# control.net
KiCad netlist of a schematic drawn in EAGLE
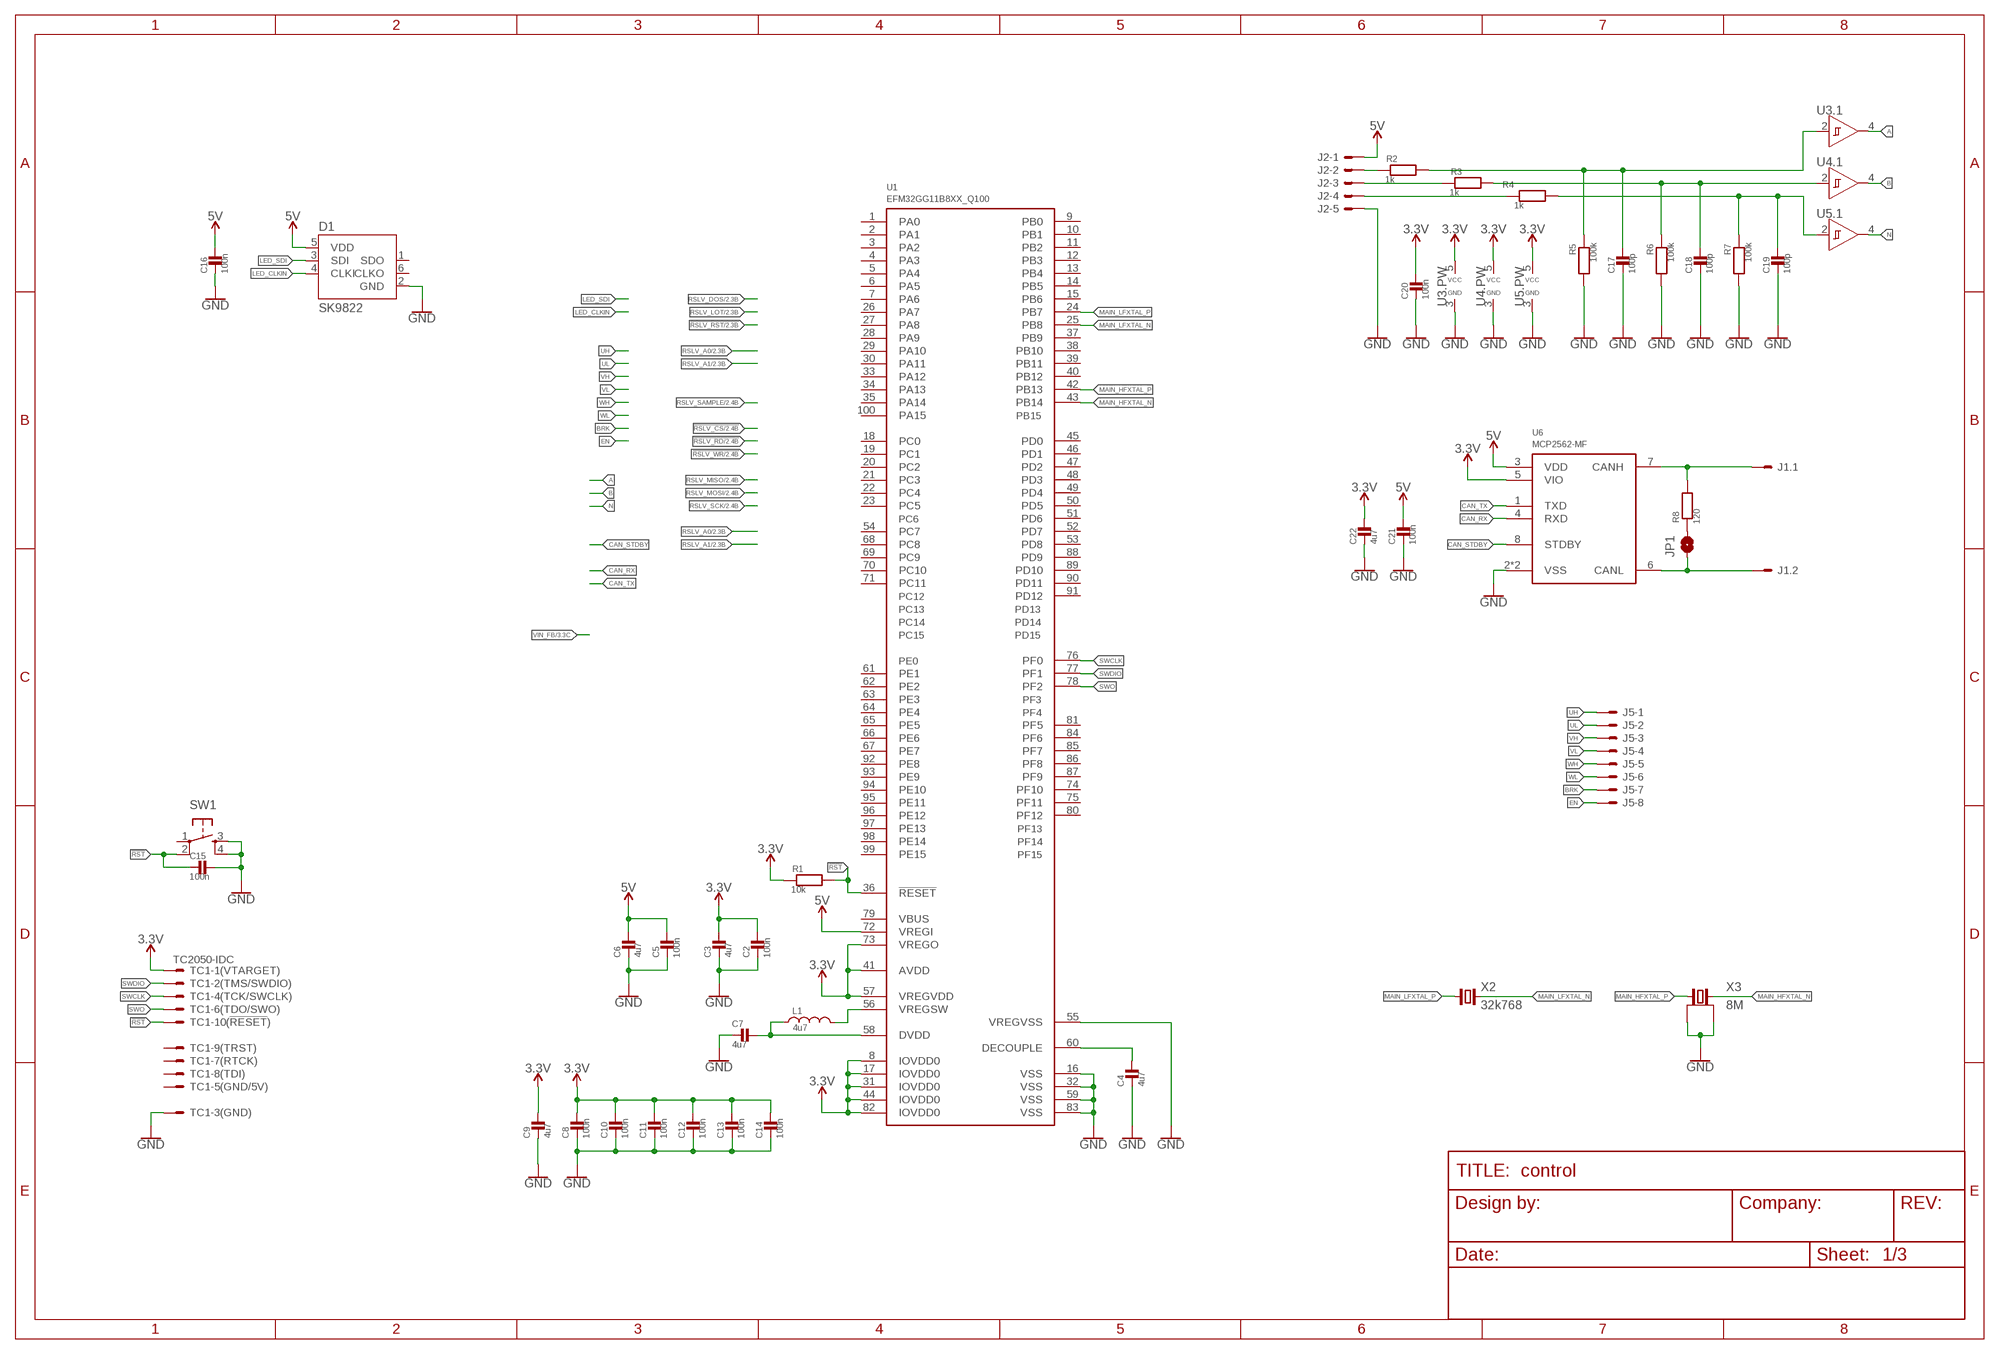
[diagram p0: schematic, sheet 1]
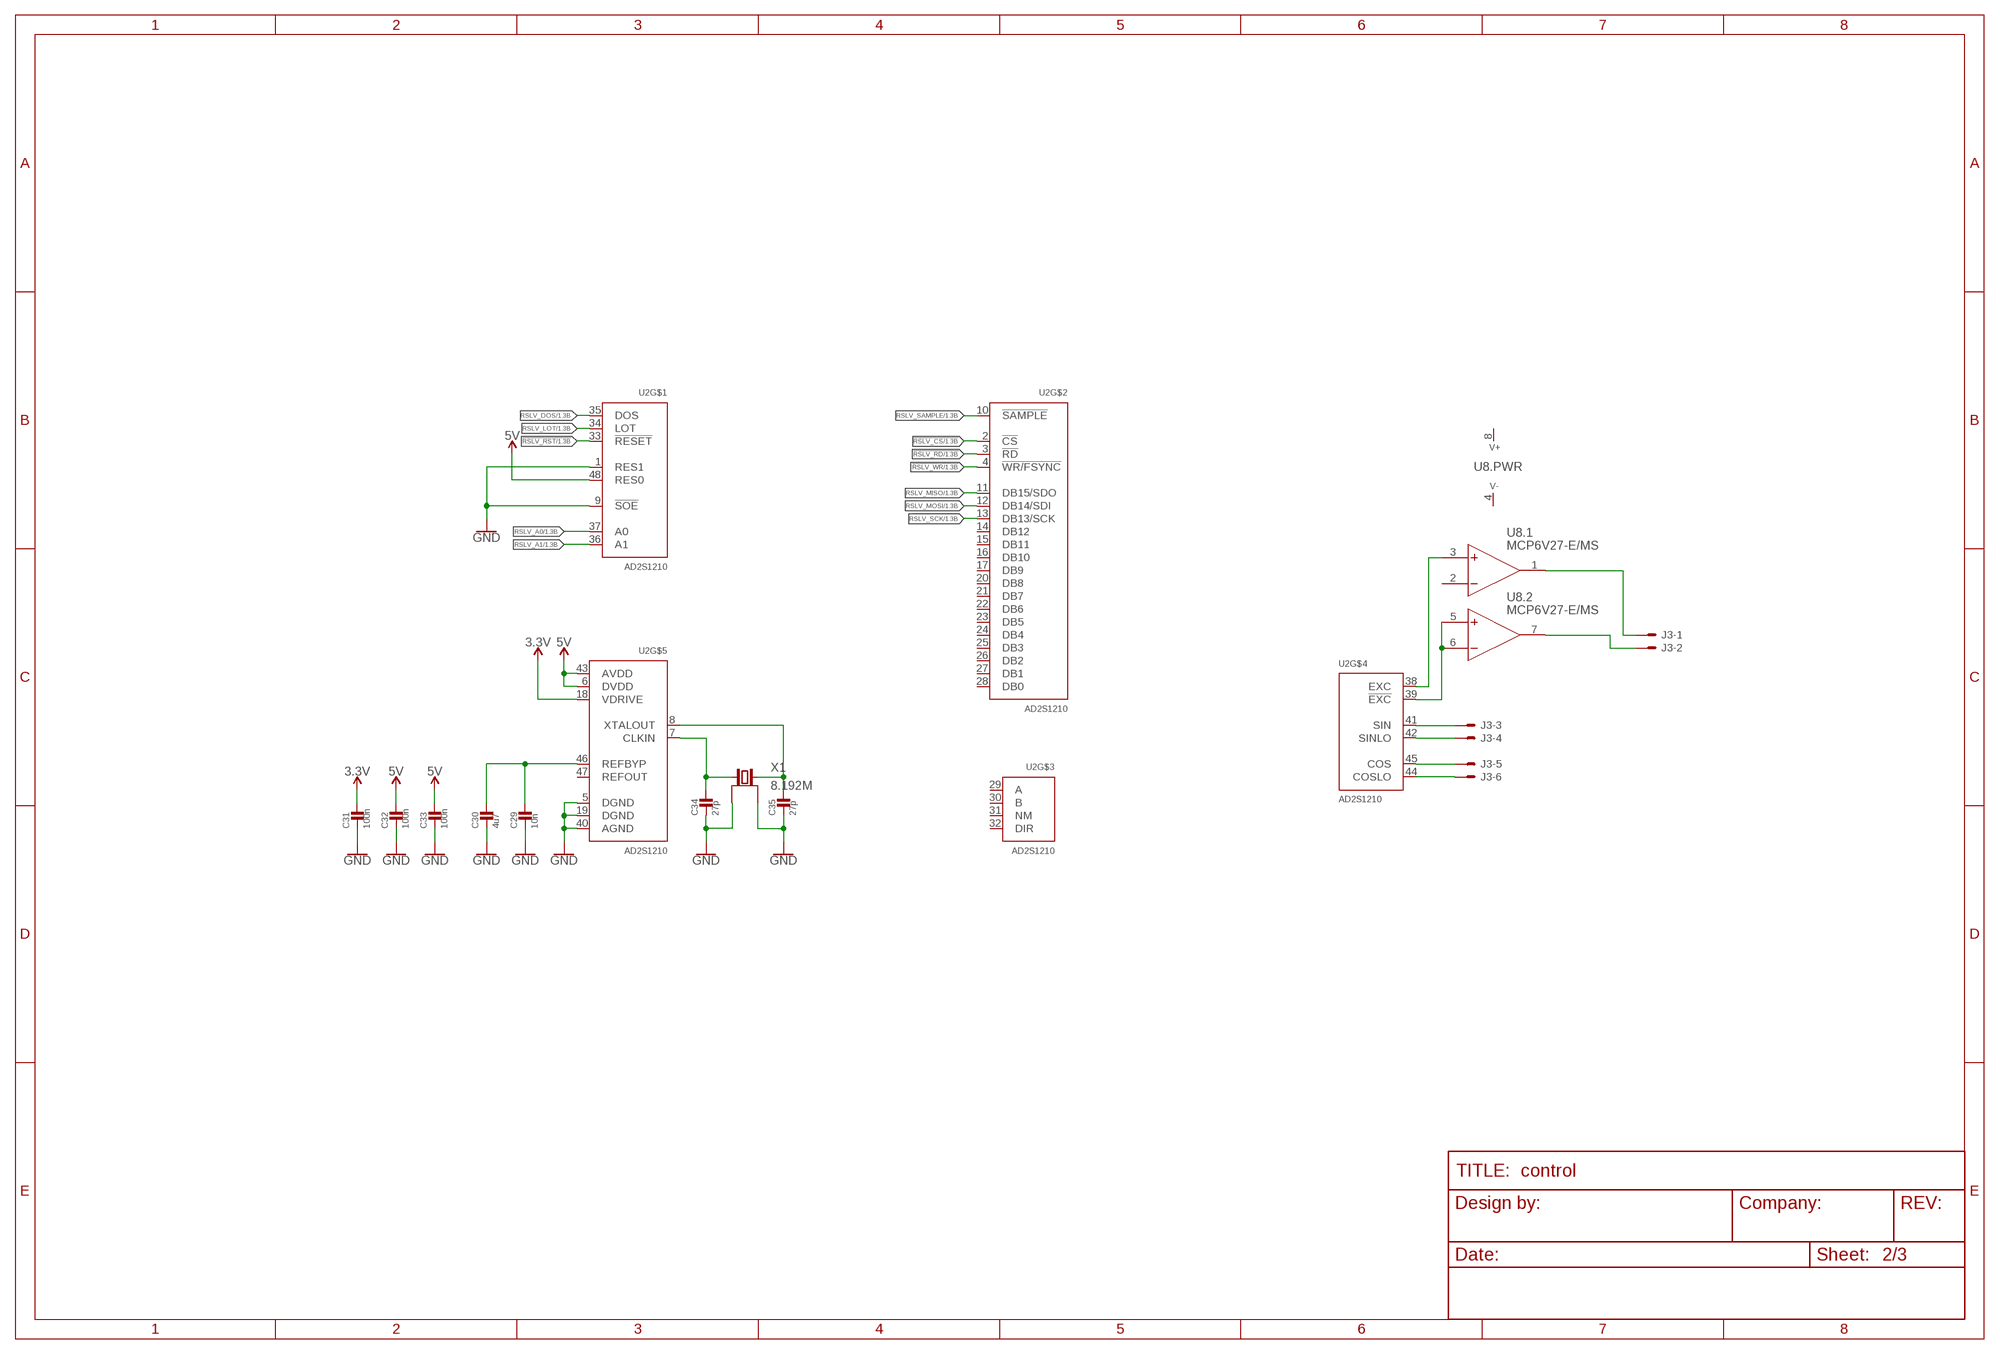
[diagram p1: schematic, sheet 2]
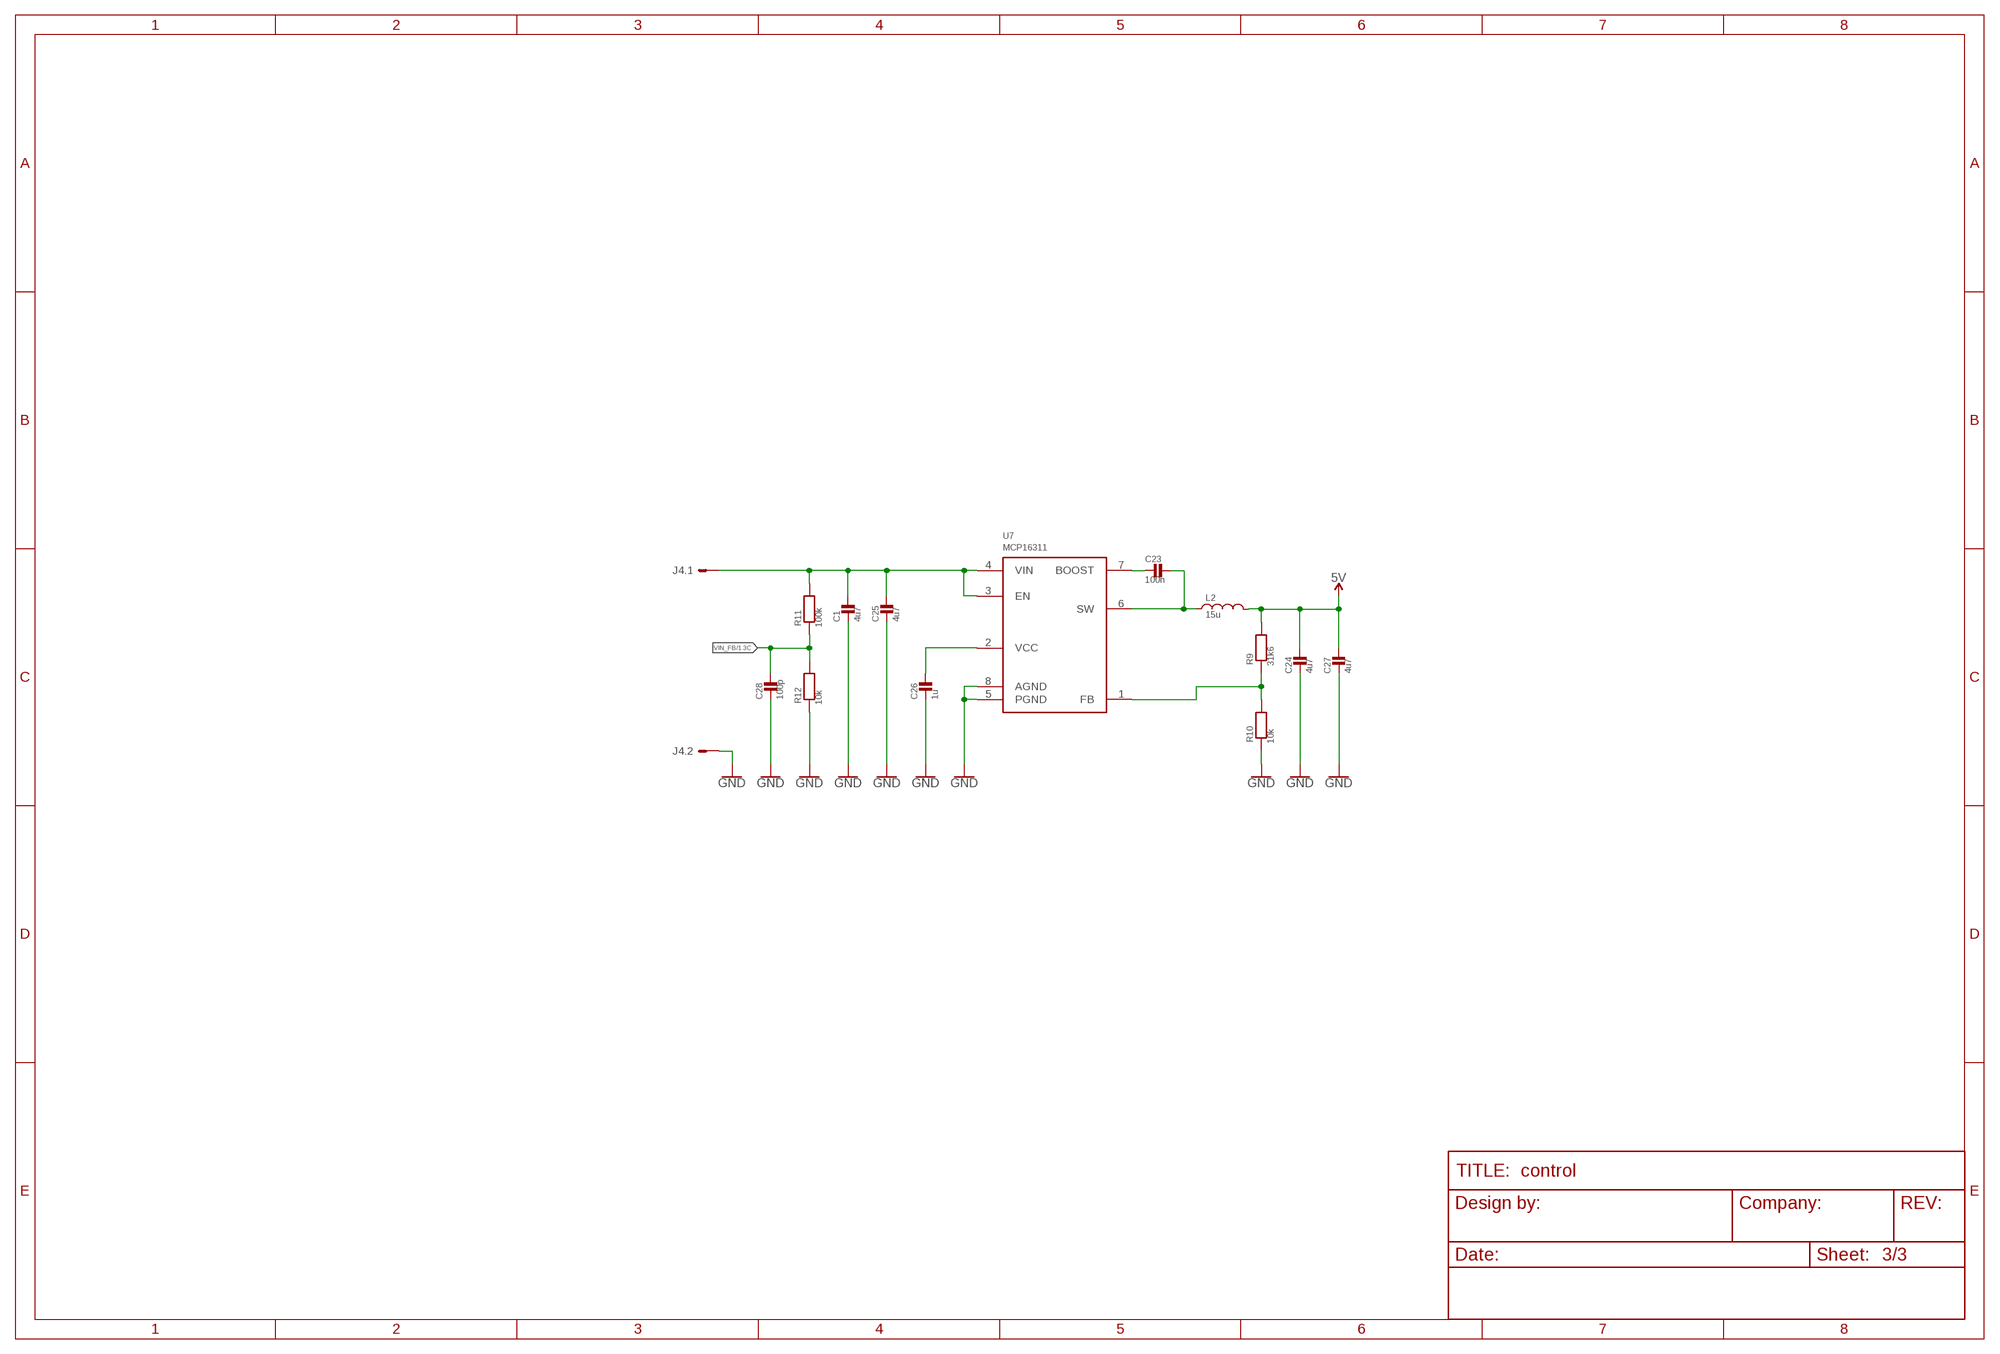
[diagram p2: schematic, sheet 3]

(export (version "E")
  (design (tool "Eeschema 10.0.6"))
  (components
    (comp (ref "C1")
      (value "4u7")
      (footprint "eagle-import:0603_WAVE")
      (libsource (lib "eagle-import") (part "MLCC0603"))
    )
    (comp (ref "C23")
      (value "100n")
      (footprint "eagle-import:0603_WAVE")
      (libsource (lib "eagle-import") (part "MLCC0603"))
    )
    (comp (ref "C24")
      (value "4u7")
      (footprint "eagle-import:0603_WAVE")
      (libsource (lib "eagle-import") (part "MLCC0603"))
    )
    (comp (ref "C25")
      (value "4u7")
      (footprint "eagle-import:0603_WAVE")
      (libsource (lib "eagle-import") (part "MLCC0603"))
    )
    (comp (ref "C26")
      (value "1u")
      (footprint "eagle-import:0603_WAVE")
      (libsource (lib "eagle-import") (part "MLCC0603"))
    )
    (comp (ref "C27")
      (value "4u7")
      (footprint "eagle-import:0603_WAVE")
      (libsource (lib "eagle-import") (part "MLCC0603"))
    )
    (comp (ref "C28")
      (value "100p")
      (footprint "eagle-import:0603_WAVE")
      (libsource (lib "eagle-import") (part "MLCC0603"))
    )
    (comp (ref "J4")
      (value "2EDG-2P")
      (footprint "eagle-import:2EDG-2P")
      (libsource (lib "eagle-import") (part "2EDG-2P"))
    )
    (comp (ref "L2")
      (value "15u")
      (footprint "eagle-import:_0806")
      (libsource (lib "eagle-import") (part "INDUCTOR_NC_0806"))
    )
    (comp (ref "R9")
      (value "31k6")
      (footprint "eagle-import:0603_WAVE")
      (libsource (lib "eagle-import") (part "RESISTOR0603"))
    )
    (comp (ref "R10")
      (value "10k")
      (footprint "eagle-import:0603_WAVE")
      (libsource (lib "eagle-import") (part "RESISTOR0603"))
    )
    (comp (ref "R11")
      (value "100k")
      (footprint "eagle-import:0603_WAVE")
      (libsource (lib "eagle-import") (part "RESISTOR0603"))
    )
    (comp (ref "R12")
      (value "10k")
      (footprint "eagle-import:0603_WAVE")
      (libsource (lib "eagle-import") (part "RESISTOR0603"))
    )
    (comp (ref "U7")
      (value "MCP16311")
      (footprint "eagle-import:MSOP8")
      (libsource (lib "eagle-import") (part "MCP16311"))
    )
    (comp (ref "C29")
      (value "10n")
      (footprint "eagle-import:0603_WAVE")
      (libsource (lib "eagle-import") (part "MLCC0603"))
    )
    (comp (ref "C30")
      (value "4u7")
      (footprint "eagle-import:0603_WAVE")
      (libsource (lib "eagle-import") (part "MLCC0603"))
    )
    (comp (ref "C31")
      (value "100n")
      (footprint "eagle-import:0603_WAVE")
      (libsource (lib "eagle-import") (part "MLCC0603"))
    )
    (comp (ref "C32")
      (value "100n")
      (footprint "eagle-import:0603_WAVE")
      (libsource (lib "eagle-import") (part "MLCC0603"))
    )
    (comp (ref "C33")
      (value "100n")
      (footprint "eagle-import:0603_WAVE")
      (libsource (lib "eagle-import") (part "MLCC0603"))
    )
    (comp (ref "C34")
      (value "27p")
      (footprint "eagle-import:0603_WAVE")
      (libsource (lib "eagle-import") (part "MLCC0603"))
    )
    (comp (ref "C35")
      (value "27p")
      (footprint "eagle-import:0603_WAVE")
      (libsource (lib "eagle-import") (part "MLCC0603"))
    )
    (comp (ref "J3")
      (value "6")
      (footprint "eagle-import:1X6_2.54")
      (libsource (lib "eagle-import") (part "6"))
    )
    (comp (ref "U2")
      (value "AD2S1210")
      (footprint "eagle-import:QFP64")
      (libsource (lib "eagle-import") (part "AD2S1210"))
    )
    (comp (ref "U8")
      (value "MCP6V27-E/MS")
      (footprint "eagle-import:MSOP-8")
      (libsource (lib "eagle-import") (part "MCP6V27-E/MS"))
    )
    (comp (ref "X1")
      (value "8.192M")
      (footprint "eagle-import:4-SMD-3225")
      (libsource (lib "eagle-import") (part "CRYSTAL_4P"))
    )
    (comp (ref "C2")
      (value "100n")
      (footprint "eagle-import:0603_WAVE")
      (libsource (lib "eagle-import") (part "MLCC0603"))
    )
    (comp (ref "C3")
      (value "4u7")
      (footprint "eagle-import:0603_WAVE")
      (libsource (lib "eagle-import") (part "MLCC0603"))
    )
    (comp (ref "C4")
      (value "4u7")
      (footprint "eagle-import:0603_WAVE")
      (libsource (lib "eagle-import") (part "MLCC0603"))
    )
    (comp (ref "C5")
      (value "100n")
      (footprint "eagle-import:0603_WAVE")
      (libsource (lib "eagle-import") (part "MLCC0603"))
    )
    (comp (ref "C6")
      (value "4u7")
      (footprint "eagle-import:0603_WAVE")
      (libsource (lib "eagle-import") (part "MLCC0603"))
    )
    (comp (ref "C7")
      (value "4u7")
      (footprint "eagle-import:0603_WAVE")
      (libsource (lib "eagle-import") (part "MLCC0603"))
    )
    (comp (ref "C8")
      (value "100n")
      (footprint "eagle-import:0603_WAVE")
      (libsource (lib "eagle-import") (part "MLCC0603"))
    )
    (comp (ref "C9")
      (value "4u7")
      (footprint "eagle-import:0603_WAVE")
      (libsource (lib "eagle-import") (part "MLCC0603"))
    )
    (comp (ref "C10")
      (value "100n")
      (footprint "eagle-import:0603_WAVE")
      (libsource (lib "eagle-import") (part "MLCC0603"))
    )
    (comp (ref "C11")
      (value "100n")
      (footprint "eagle-import:0603_WAVE")
      (libsource (lib "eagle-import") (part "MLCC0603"))
    )
    (comp (ref "C12")
      (value "100n")
      (footprint "eagle-import:0603_WAVE")
      (libsource (lib "eagle-import") (part "MLCC0603"))
    )
    (comp (ref "C13")
      (value "100n")
      (footprint "eagle-import:0603_WAVE")
      (libsource (lib "eagle-import") (part "MLCC0603"))
    )
    (comp (ref "C14")
      (value "100n")
      (footprint "eagle-import:0603_WAVE")
      (libsource (lib "eagle-import") (part "MLCC0603"))
    )
    (comp (ref "C15")
      (value "100n")
      (footprint "eagle-import:0603_WAVE")
      (libsource (lib "eagle-import") (part "MLCC0603"))
    )
    (comp (ref "C16")
      (value "100n")
      (footprint "eagle-import:0603_WAVE")
      (libsource (lib "eagle-import") (part "MLCC0603"))
    )
    (comp (ref "C17")
      (value "100p")
      (footprint "eagle-import:0603_WAVE")
      (libsource (lib "eagle-import") (part "MLCC0603"))
    )
    (comp (ref "C18")
      (value "100p")
      (footprint "eagle-import:0603_WAVE")
      (libsource (lib "eagle-import") (part "MLCC0603"))
    )
    (comp (ref "C19")
      (value "100p")
      (footprint "eagle-import:0603_WAVE")
      (libsource (lib "eagle-import") (part "MLCC0603"))
    )
    (comp (ref "C20")
      (value "100n")
      (footprint "eagle-import:0603_WAVE")
      (libsource (lib "eagle-import") (part "MLCC0603"))
    )
    (comp (ref "C21")
      (value "100n")
      (footprint "eagle-import:0603_WAVE")
      (libsource (lib "eagle-import") (part "MLCC0603"))
    )
    (comp (ref "C22")
      (value "4u7")
      (footprint "eagle-import:0603_WAVE")
      (libsource (lib "eagle-import") (part "MLCC0603"))
    )
    (comp (ref "D1")
      (value "SK9822")
      (footprint "eagle-import:2020")
      (libsource (lib "eagle-import") (part "SK9822"))
    )
    (comp (ref "J1")
      (value "2EDG-2P")
      (footprint "eagle-import:2EDG-2P")
      (libsource (lib "eagle-import") (part "2EDG-2P"))
    )
    (comp (ref "J2")
      (value "5")
      (footprint "eagle-import:1X5_2.54")
      (libsource (lib "eagle-import") (part "5"))
    )
    (comp (ref "J5")
      (value "8")
      (footprint "eagle-import:1X8_2.54")
      (libsource (lib "eagle-import") (part "8"))
    )
    (comp (ref "JP1")
      (value "JUMPER-SMT_2_NO_NO-SILK")
      (footprint "eagle-import:SMT-JUMPER_2_NO_NO-SILK")
      (libsource (lib "eagle-import") (part "JUMPER-SMT_2_NO_NO-SILK"))
    )
    (comp (ref "L1")
      (value "4u7")
      (footprint "eagle-import:_0806")
      (libsource (lib "eagle-import") (part "INDUCTOR_NC_0806"))
    )
    (comp (ref "R1")
      (value "10k")
      (footprint "eagle-import:0603_WAVE")
      (libsource (lib "eagle-import") (part "RESISTOR0603"))
    )
    (comp (ref "R2")
      (value "1k")
      (footprint "eagle-import:0603_WAVE")
      (libsource (lib "eagle-import") (part "RESISTOR0603"))
    )
    (comp (ref "R3")
      (value "1k")
      (footprint "eagle-import:0603_WAVE")
      (libsource (lib "eagle-import") (part "RESISTOR0603"))
    )
    (comp (ref "R4")
      (value "1k")
      (footprint "eagle-import:0603_WAVE")
      (libsource (lib "eagle-import") (part "RESISTOR0603"))
    )
    (comp (ref "R5")
      (value "100k")
      (footprint "eagle-import:0603_WAVE")
      (libsource (lib "eagle-import") (part "RESISTOR0603"))
    )
    (comp (ref "R6")
      (value "100k")
      (footprint "eagle-import:0603_WAVE")
      (libsource (lib "eagle-import") (part "RESISTOR0603"))
    )
    (comp (ref "R7")
      (value "100k")
      (footprint "eagle-import:0603_WAVE")
      (libsource (lib "eagle-import") (part "RESISTOR0603"))
    )
    (comp (ref "R8")
      (value "120")
      (footprint "eagle-import:0603_WAVE")
      (libsource (lib "eagle-import") (part "RESISTOR0603"))
    )
    (comp (ref "SW1")
      (value "PUSH_BUTTON")
      (footprint "eagle-import:PUSH_BUTTON")
      (libsource (lib "eagle-import") (part "PUSH_BUTTON"))
    )
    (comp (ref "TC1")
      (value "TC2050-IDC")
      (footprint "eagle-import:TC2050-IDC")
      (libsource (lib "eagle-import") (part "TC2050-IDC"))
    )
    (comp (ref "U1")
      (value "EFM32GG11B8XX_Q100")
      (footprint "eagle-import:QFP100")
      (libsource (lib "eagle-import") (part "EFM32GG11B8XX_Q100"))
    )
    (comp (ref "U3")
      (value "74LVC1G17")
      (footprint "eagle-import:SC70-5")
      (libsource (lib "eagle-import") (part "74LVC1G17"))
    )
    (comp (ref "U4")
      (value "74LVC1G17")
      (footprint "eagle-import:SC70-5")
      (libsource (lib "eagle-import") (part "74LVC1G17"))
    )
    (comp (ref "U5")
      (value "74LVC1G17")
      (footprint "eagle-import:SC70-5")
      (libsource (lib "eagle-import") (part "74LVC1G17"))
    )
    (comp (ref "U6")
      (value "MCP2562-MF")
      (footprint "eagle-import:DFN8")
      (libsource (lib "eagle-import") (part "MCP2562-MF"))
    )
    (comp (ref "X2")
      (value "32k768")
      (footprint "eagle-import:2-SMD-3215")
      (libsource (lib "eagle-import") (part "CRYSTAL2-SMD-3215"))
    )
    (comp (ref "X3")
      (value "8M")
      (footprint "eagle-import:4-SMD-3225")
      (libsource (lib "eagle-import") (part "CRYSTAL_4P"))
    )
  )
  (nets
    (net (code "1") (name "3.3V") (class "Default")
      (node (ref "C10") (pin "P$1") (pinfunction "P$1_P$1") (pintype "bidirectional"))
      (node (ref "C11") (pin "P$1") (pinfunction "P$1_P$1") (pintype "bidirectional"))
      (node (ref "C12") (pin "P$1") (pinfunction "P$1_P$1") (pintype "bidirectional"))
      (node (ref "C13") (pin "P$1") (pinfunction "P$1_P$1") (pintype "bidirectional"))
      (node (ref "C14") (pin "P$1") (pinfunction "P$1_P$1") (pintype "bidirectional"))
      (node (ref "C2") (pin "P$1") (pinfunction "P$1_P$1") (pintype "bidirectional"))
      (node (ref "C20") (pin "P$1") (pinfunction "P$1_P$1") (pintype "bidirectional"))
      (node (ref "C22") (pin "P$1") (pinfunction "P$1_P$1") (pintype "bidirectional"))
      (node (ref "C3") (pin "P$1") (pinfunction "P$1_P$1") (pintype "bidirectional"))
      (node (ref "C31") (pin "P$1") (pinfunction "P$1_P$1") (pintype "bidirectional"))
      (node (ref "C8") (pin "P$1") (pinfunction "P$1_P$1") (pintype "bidirectional"))
      (node (ref "C9") (pin "P$1") (pinfunction "P$1_P$1") (pintype "bidirectional"))
      (node (ref "R1") (pin "P$1") (pinfunction "P$1_P$1") (pintype "bidirectional"))
      (node (ref "TC1") (pin "1") (pinfunction "S_1") (pintype "passive"))
      (node (ref "U1") (pin "17") (pinfunction "IOVDD0_17") (pintype "bidirectional"))
      (node (ref "U1") (pin "31") (pinfunction "IOVDD0_31") (pintype "bidirectional"))
      (node (ref "U1") (pin "41") (pinfunction "AVDD_41") (pintype "bidirectional"))
      (node (ref "U1") (pin "44") (pinfunction "IOVDD0_44") (pintype "bidirectional"))
      (node (ref "U1") (pin "57") (pinfunction "VREGVDD_57") (pintype "bidirectional"))
      (node (ref "U1") (pin "73") (pinfunction "VREGO_73") (pintype "bidirectional"))
      (node (ref "U1") (pin "8") (pinfunction "IOVDD0_8") (pintype "bidirectional"))
      (node (ref "U1") (pin "82") (pinfunction "IOVDD0_82") (pintype "bidirectional"))
      (node (ref "U2") (pin "18") (pinfunction "VDRIVE_18") (pintype "bidirectional"))
      (node (ref "U3") (pin "5") (pinfunction "VCC_5") (pintype "bidirectional"))
      (node (ref "U4") (pin "5") (pinfunction "VCC_5") (pintype "bidirectional"))
      (node (ref "U5") (pin "5") (pinfunction "VCC_5") (pintype "bidirectional"))
      (node (ref "U6") (pin "5") (pinfunction "VIO_5") (pintype "power_in"))
    )
    (net (code "2") (name "5V") (class "Default")
      (node (ref "C16") (pin "P$1") (pinfunction "P$1_P$1") (pintype "bidirectional"))
      (node (ref "C21") (pin "P$1") (pinfunction "P$1_P$1") (pintype "bidirectional"))
      (node (ref "C24") (pin "P$1") (pinfunction "P$1_P$1") (pintype "bidirectional"))
      (node (ref "C27") (pin "P$1") (pinfunction "P$1_P$1") (pintype "bidirectional"))
      (node (ref "C32") (pin "P$1") (pinfunction "P$1_P$1") (pintype "bidirectional"))
      (node (ref "C33") (pin "P$1") (pinfunction "P$1_P$1") (pintype "bidirectional"))
      (node (ref "C5") (pin "P$1") (pinfunction "P$1_P$1") (pintype "bidirectional"))
      (node (ref "C6") (pin "P$1") (pinfunction "P$1_P$1") (pintype "bidirectional"))
      (node (ref "D1") (pin "5") (pinfunction "VDD_5") (pintype "bidirectional"))
      (node (ref "J2") (pin "1") (pinfunction "S_1") (pintype "passive"))
      (node (ref "L2") (pin "2") (pinfunction "P$2_2") (pintype "bidirectional"))
      (node (ref "R9") (pin "P$2") (pinfunction "P$2_P$2") (pintype "bidirectional"))
      (node (ref "U1") (pin "72") (pinfunction "VREGI_72") (pintype "bidirectional"))
      (node (ref "U2") (pin "43") (pinfunction "AVDD_43") (pintype "bidirectional"))
      (node (ref "U2") (pin "48") (pinfunction "RES0_48") (pintype "bidirectional"))
      (node (ref "U2") (pin "6") (pinfunction "DVDD_6") (pintype "bidirectional"))
      (node (ref "U6") (pin "3") (pinfunction "VDD_3") (pintype "power_in"))
    )
    (net (code "3") (name "A") (class "Default")
      (node (ref "U3") (pin "4") (pinfunction "Y_4") (pintype "output"))
    )
    (net (code "4") (name "B") (class "Default")
      (node (ref "U4") (pin "4") (pinfunction "Y_4") (pintype "output"))
    )
    (net (code "5") (name "BRK") (class "Default")
      (node (ref "J5") (pin "7") (pinfunction "S_7") (pintype "passive"))
    )
    (net (code "6") (name "CAN_RX") (class "Default")
      (node (ref "U6") (pin "4") (pinfunction "RXD_4") (pintype "bidirectional"))
    )
    (net (code "7") (name "CAN_STDBY") (class "Default")
      (node (ref "U6") (pin "8") (pinfunction "STDBY_8") (pintype "bidirectional"))
    )
    (net (code "8") (name "CAN_TX") (class "Default")
      (node (ref "U6") (pin "1") (pinfunction "TXD_1") (pintype "bidirectional"))
    )
    (net (code "9") (name "EN") (class "Default")
      (node (ref "J5") (pin "8") (pinfunction "S_8") (pintype "passive"))
    )
    (net (code "10") (name "GND") (class "Default")
      (node (ref "C1") (pin "P$2") (pinfunction "P$2_P$2") (pintype "bidirectional"))
      (node (ref "C10") (pin "P$2") (pinfunction "P$2_P$2") (pintype "bidirectional"))
      (node (ref "C11") (pin "P$2") (pinfunction "P$2_P$2") (pintype "bidirectional"))
      (node (ref "C12") (pin "P$2") (pinfunction "P$2_P$2") (pintype "bidirectional"))
      (node (ref "C13") (pin "P$2") (pinfunction "P$2_P$2") (pintype "bidirectional"))
      (node (ref "C14") (pin "P$2") (pinfunction "P$2_P$2") (pintype "bidirectional"))
      (node (ref "C15") (pin "P$1") (pinfunction "P$1_P$1") (pintype "bidirectional"))
      (node (ref "C16") (pin "P$2") (pinfunction "P$2_P$2") (pintype "bidirectional"))
      (node (ref "C17") (pin "P$2") (pinfunction "P$2_P$2") (pintype "bidirectional"))
      (node (ref "C18") (pin "P$2") (pinfunction "P$2_P$2") (pintype "bidirectional"))
      (node (ref "C19") (pin "P$2") (pinfunction "P$2_P$2") (pintype "bidirectional"))
      (node (ref "C2") (pin "P$2") (pinfunction "P$2_P$2") (pintype "bidirectional"))
      (node (ref "C20") (pin "P$2") (pinfunction "P$2_P$2") (pintype "bidirectional"))
      (node (ref "C21") (pin "P$2") (pinfunction "P$2_P$2") (pintype "bidirectional"))
      (node (ref "C22") (pin "P$2") (pinfunction "P$2_P$2") (pintype "bidirectional"))
      (node (ref "C24") (pin "P$2") (pinfunction "P$2_P$2") (pintype "bidirectional"))
      (node (ref "C25") (pin "P$2") (pinfunction "P$2_P$2") (pintype "bidirectional"))
      (node (ref "C26") (pin "P$2") (pinfunction "P$2_P$2") (pintype "bidirectional"))
      (node (ref "C27") (pin "P$2") (pinfunction "P$2_P$2") (pintype "bidirectional"))
      (node (ref "C28") (pin "P$2") (pinfunction "P$2_P$2") (pintype "bidirectional"))
      (node (ref "C29") (pin "P$2") (pinfunction "P$2_P$2") (pintype "bidirectional"))
      (node (ref "C3") (pin "P$2") (pinfunction "P$2_P$2") (pintype "bidirectional"))
      (node (ref "C30") (pin "P$2") (pinfunction "P$2_P$2") (pintype "bidirectional"))
      (node (ref "C31") (pin "P$2") (pinfunction "P$2_P$2") (pintype "bidirectional"))
      (node (ref "C32") (pin "P$2") (pinfunction "P$2_P$2") (pintype "bidirectional"))
      (node (ref "C33") (pin "P$2") (pinfunction "P$2_P$2") (pintype "bidirectional"))
      (node (ref "C34") (pin "P$2") (pinfunction "P$2_P$2") (pintype "bidirectional"))
      (node (ref "C35") (pin "P$2") (pinfunction "P$2_P$2") (pintype "bidirectional"))
      (node (ref "C4") (pin "P$2") (pinfunction "P$2_P$2") (pintype "bidirectional"))
      (node (ref "C5") (pin "P$2") (pinfunction "P$2_P$2") (pintype "bidirectional"))
      (node (ref "C6") (pin "P$2") (pinfunction "P$2_P$2") (pintype "bidirectional"))
      (node (ref "C7") (pin "P$2") (pinfunction "P$2_P$2") (pintype "bidirectional"))
      (node (ref "C8") (pin "P$2") (pinfunction "P$2_P$2") (pintype "bidirectional"))
      (node (ref "C9") (pin "P$2") (pinfunction "P$2_P$2") (pintype "bidirectional"))
      (node (ref "D1") (pin "2") (pinfunction "GND_2") (pintype "bidirectional"))
      (node (ref "J2") (pin "5") (pinfunction "S_5") (pintype "passive"))
      (node (ref "J4") (pin "P$2") (pinfunction "S_P$2") (pintype "passive"))
      (node (ref "R10") (pin "P$1") (pinfunction "P$1_P$1") (pintype "bidirectional"))
      (node (ref "R12") (pin "P$1") (pinfunction "P$1_P$1") (pintype "bidirectional"))
      (node (ref "R5") (pin "P$2") (pinfunction "P$2_P$2") (pintype "bidirectional"))
      (node (ref "R6") (pin "P$2") (pinfunction "P$2_P$2") (pintype "bidirectional"))
      (node (ref "R7") (pin "P$2") (pinfunction "P$2_P$2") (pintype "bidirectional"))
      (node (ref "SW1") (pin "3") (pinfunction "3_3") (pintype "passive"))
      (node (ref "SW1") (pin "4") (pinfunction "4_4") (pintype "passive"))
      (node (ref "TC1") (pin "3") (pinfunction "S_3") (pintype "passive"))
      (node (ref "U1") (pin "16") (pinfunction "VSS_16") (pintype "bidirectional"))
      (node (ref "U1") (pin "32") (pinfunction "VSS_32") (pintype "bidirectional"))
      (node (ref "U1") (pin "55") (pinfunction "VREGVSS_55") (pintype "bidirectional"))
      (node (ref "U1") (pin "59") (pinfunction "VSS_59") (pintype "bidirectional"))
      (node (ref "U1") (pin "83") (pinfunction "VSS_83") (pintype "bidirectional"))
      (node (ref "U2") (pin "1") (pinfunction "RES1_1") (pintype "bidirectional"))
      (node (ref "U2") (pin "19") (pinfunction "DGND_19") (pintype "bidirectional"))
      (node (ref "U2") (pin "40") (pinfunction "AGND_40") (pintype "bidirectional"))
      (node (ref "U2") (pin "5") (pinfunction "DGND_5") (pintype "bidirectional"))
      (node (ref "U2") (pin "9") (pinfunction "~{SOE}_9") (pintype "bidirectional"))
      (node (ref "U3") (pin "3") (pinfunction "GND_3") (pintype "bidirectional"))
      (node (ref "U4") (pin "3") (pinfunction "GND_3") (pintype "bidirectional"))
      (node (ref "U5") (pin "3") (pinfunction "GND_3") (pintype "bidirectional"))
      (node (ref "U6") (pin "2") (pinfunction "VSS_2") (pintype "power_in"))
      (node (ref "U6") (pin "9") (pinfunction "VSS_9") (pintype "power_in"))
      (node (ref "U7") (pin "5") (pinfunction "PGND_5") (pintype "bidirectional"))
      (node (ref "U7") (pin "8") (pinfunction "AGND_8") (pintype "bidirectional"))
      (node (ref "X1") (pin "2") (pinfunction "GND_2") (pintype "passive"))
      (node (ref "X1") (pin "4") (pinfunction "GND_4") (pintype "passive"))
      (node (ref "X3") (pin "2") (pinfunction "GND_2") (pintype "passive"))
      (node (ref "X3") (pin "4") (pinfunction "GND_4") (pintype "passive"))
    )
    (net (code "11") (name "LED_CLKIN") (class "Default")
      (node (ref "D1") (pin "4") (pinfunction "CLKI_4") (pintype "bidirectional"))
    )
    (net (code "12") (name "LED_SDI") (class "Default")
      (node (ref "D1") (pin "3") (pinfunction "SDI_3") (pintype "bidirectional"))
    )
    (net (code "13") (name "MAIN_HFXTAL_N") (class "Default")
      (node (ref "U1") (pin "43") (pinfunction "PB14_43") (pintype "bidirectional"))
      (node (ref "X3") (pin "3") (pinfunction "2_3") (pintype "passive"))
    )
    (net (code "14") (name "MAIN_HFXTAL_P") (class "Default")
      (node (ref "U1") (pin "42") (pinfunction "PB13_42") (pintype "bidirectional"))
      (node (ref "X3") (pin "1") (pinfunction "1_1") (pintype "passive"))
    )
    (net (code "15") (name "MAIN_LFXTAL_N") (class "Default")
      (node (ref "U1") (pin "25") (pinfunction "PB8_25") (pintype "bidirectional"))
      (node (ref "X2") (pin "2") (pinfunction "2_2") (pintype "passive"))
    )
    (net (code "16") (name "MAIN_LFXTAL_P") (class "Default")
      (node (ref "U1") (pin "24") (pinfunction "PB7_24") (pintype "bidirectional"))
      (node (ref "X2") (pin "1") (pinfunction "1_1") (pintype "passive"))
    )
    (net (code "17") (name "N") (class "Default")
      (node (ref "U5") (pin "4") (pinfunction "Y_4") (pintype "output"))
    )
    (net (code "18") (name "Net-(J1A-S)") (class "Default")
      (node (ref "J1") (pin "P$1") (pinfunction "S_P$1") (pintype "passive"))
      (node (ref "R8") (pin "P$2") (pinfunction "P$2_P$2") (pintype "bidirectional"))
      (node (ref "U6") (pin "7") (pinfunction "CANH_7") (pintype "bidirectional"))
    )
    (net (code "19") (name "Net-(J1B-S)") (class "Default")
      (node (ref "J1") (pin "P$2") (pinfunction "S_P$2") (pintype "passive"))
      (node (ref "JP1") (pin "1") (pinfunction "1_1") (pintype "passive"))
      (node (ref "U6") (pin "6") (pinfunction "CANL_6") (pintype "bidirectional"))
    )
    (net (code "20") (name "Net-(J2B-S)") (class "Default")
      (node (ref "J2") (pin "2") (pinfunction "S_2") (pintype "passive"))
      (node (ref "R2") (pin "P$1") (pinfunction "P$1_P$1") (pintype "bidirectional"))
    )
    (net (code "21") (name "Net-(J2C-S)") (class "Default")
      (node (ref "J2") (pin "3") (pinfunction "S_3") (pintype "passive"))
      (node (ref "R3") (pin "P$1") (pinfunction "P$1_P$1") (pintype "bidirectional"))
    )
    (net (code "22") (name "Net-(J2D-S)") (class "Default")
      (node (ref "J2") (pin "4") (pinfunction "S_4") (pintype "passive"))
      (node (ref "R4") (pin "P$1") (pinfunction "P$1_P$1") (pintype "bidirectional"))
    )
    (net (code "23") (name "Net-(J3A-S)") (class "Default")
      (node (ref "J3") (pin "1") (pinfunction "S_1") (pintype "passive"))
      (node (ref "U8") (pin "1") (pinfunction "OUT_1") (pintype "output"))
    )
    (net (code "24") (name "Net-(J3B-S)") (class "Default")
      (node (ref "J3") (pin "2") (pinfunction "S_2") (pintype "passive"))
      (node (ref "U8") (pin "7") (pinfunction "OUT_7") (pintype "output"))
    )
    (net (code "25") (name "Net-(J3C-S)") (class "Default")
      (node (ref "J3") (pin "3") (pinfunction "S_3") (pintype "passive"))
      (node (ref "U2") (pin "41") (pinfunction "SIN_41") (pintype "bidirectional"))
    )
    (net (code "26") (name "Net-(J3D-S)") (class "Default")
      (node (ref "J3") (pin "4") (pinfunction "S_4") (pintype "passive"))
      (node (ref "U2") (pin "42") (pinfunction "SINLO_42") (pintype "bidirectional"))
    )
    (net (code "27") (name "Net-(J3E-S)") (class "Default")
      (node (ref "J3") (pin "5") (pinfunction "S_5") (pintype "passive"))
      (node (ref "U2") (pin "45") (pinfunction "COS_45") (pintype "bidirectional"))
    )
    (net (code "28") (name "Net-(J3F-S)") (class "Default")
      (node (ref "J3") (pin "6") (pinfunction "S_6") (pintype "passive"))
      (node (ref "U2") (pin "44") (pinfunction "COSLO_44") (pintype "bidirectional"))
    )
    (net (code "29") (name "Net-(J4A-S)") (class "Default")
      (node (ref "C1") (pin "P$1") (pinfunction "P$1_P$1") (pintype "bidirectional"))
      (node (ref "C25") (pin "P$1") (pinfunction "P$1_P$1") (pintype "bidirectional"))
      (node (ref "J4") (pin "P$1") (pinfunction "S_P$1") (pintype "passive"))
      (node (ref "R11") (pin "P$2") (pinfunction "P$2_P$2") (pintype "bidirectional"))
      (node (ref "U7") (pin "3") (pinfunction "EN_3") (pintype "bidirectional"))
      (node (ref "U7") (pin "4") (pinfunction "VIN_4") (pintype "bidirectional"))
    )
    (net (code "30") (name "Net-(JP1-Pad2)") (class "Default")
      (node (ref "JP1") (pin "2") (pinfunction "2_2") (pintype "passive"))
      (node (ref "R8") (pin "P$1") (pinfunction "P$1_P$1") (pintype "bidirectional"))
    )
    (net (code "31") (name "Net-(L1-P$1)") (class "Default")
      (node (ref "C7") (pin "P$1") (pinfunction "P$1_P$1") (pintype "bidirectional"))
      (node (ref "L1") (pin "1") (pinfunction "P$1_1") (pintype "bidirectional"))
      (node (ref "U1") (pin "58") (pinfunction "DVDD_58") (pintype "bidirectional"))
    )
    (net (code "32") (name "Net-(L1-P$2)") (class "Default")
      (node (ref "L1") (pin "2") (pinfunction "P$2_2") (pintype "bidirectional"))
      (node (ref "U1") (pin "56") (pinfunction "VREGSW_56") (pintype "bidirectional"))
    )
    (net (code "33") (name "Net-(L2-P$1)") (class "Default")
      (node (ref "C23") (pin "P$1") (pinfunction "P$1_P$1") (pintype "bidirectional"))
      (node (ref "L2") (pin "1") (pinfunction "P$1_1") (pintype "bidirectional"))
      (node (ref "U7") (pin "6") (pinfunction "SW_6") (pintype "bidirectional"))
    )
    (net (code "34") (name "Net-(U1-DECOUPLE)") (class "Default")
      (node (ref "C4") (pin "P$1") (pinfunction "P$1_P$1") (pintype "bidirectional"))
      (node (ref "U1") (pin "60") (pinfunction "DECOUPLE_60") (pintype "bidirectional"))
    )
    (net (code "35") (name "Net-(U2D-EXC)") (class "Default")
      (node (ref "U2") (pin "38") (pinfunction "EXC_38") (pintype "bidirectional"))
      (node (ref "U8") (pin "3") (pinfunction "+IN_3") (pintype "input"))
    )
    (net (code "36") (name "Net-(U2D-~{EXC})") (class "Default")
      (node (ref "U2") (pin "39") (pinfunction "~{EXC}_39") (pintype "bidirectional"))
      (node (ref "U8") (pin "5") (pinfunction "+IN_5") (pintype "input"))
      (node (ref "U8") (pin "6") (pinfunction "-IN_6") (pintype "input"))
    )
    (net (code "37") (name "Net-(U2E-CLKIN)") (class "Default")
      (node (ref "C34") (pin "P$1") (pinfunction "P$1_P$1") (pintype "bidirectional"))
      (node (ref "U2") (pin "7") (pinfunction "CLKIN_7") (pintype "bidirectional"))
      (node (ref "X1") (pin "1") (pinfunction "1_1") (pintype "passive"))
    )
    (net (code "38") (name "Net-(U2E-REFBYP)") (class "Default")
      (node (ref "C29") (pin "P$1") (pinfunction "P$1_P$1") (pintype "bidirectional"))
      (node (ref "C30") (pin "P$1") (pinfunction "P$1_P$1") (pintype "bidirectional"))
      (node (ref "U2") (pin "46") (pinfunction "REFBYP_46") (pintype "bidirectional"))
    )
    (net (code "39") (name "Net-(U2E-XTALOUT)") (class "Default")
      (node (ref "C35") (pin "P$1") (pinfunction "P$1_P$1") (pintype "bidirectional"))
      (node (ref "U2") (pin "8") (pinfunction "XTALOUT_8") (pintype "bidirectional"))
      (node (ref "X1") (pin "3") (pinfunction "2_3") (pintype "passive"))
    )
    (net (code "40") (name "Net-(U3A-A)") (class "Default")
      (node (ref "C17") (pin "P$1") (pinfunction "P$1_P$1") (pintype "bidirectional"))
      (node (ref "R2") (pin "P$2") (pinfunction "P$2_P$2") (pintype "bidirectional"))
      (node (ref "R5") (pin "P$1") (pinfunction "P$1_P$1") (pintype "bidirectional"))
      (node (ref "U3") (pin "2") (pinfunction "A_2") (pintype "input"))
    )
    (net (code "41") (name "Net-(U4A-A)") (class "Default")
      (node (ref "C18") (pin "P$1") (pinfunction "P$1_P$1") (pintype "bidirectional"))
      (node (ref "R3") (pin "P$2") (pinfunction "P$2_P$2") (pintype "bidirectional"))
      (node (ref "R6") (pin "P$1") (pinfunction "P$1_P$1") (pintype "bidirectional"))
      (node (ref "U4") (pin "2") (pinfunction "A_2") (pintype "input"))
    )
    (net (code "42") (name "Net-(U5A-A)") (class "Default")
      (node (ref "C19") (pin "P$1") (pinfunction "P$1_P$1") (pintype "bidirectional"))
      (node (ref "R4") (pin "P$2") (pinfunction "P$2_P$2") (pintype "bidirectional"))
      (node (ref "R7") (pin "P$1") (pinfunction "P$1_P$1") (pintype "bidirectional"))
      (node (ref "U5") (pin "2") (pinfunction "A_2") (pintype "input"))
    )
    (net (code "43") (name "Net-(U7-BOOST)") (class "Default")
      (node (ref "C23") (pin "P$2") (pinfunction "P$2_P$2") (pintype "bidirectional"))
      (node (ref "U7") (pin "7") (pinfunction "BOOST_7") (pintype "bidirectional"))
    )
    (net (code "44") (name "Net-(U7-FB)") (class "Default")
      (node (ref "R10") (pin "P$2") (pinfunction "P$2_P$2") (pintype "bidirectional"))
      (node (ref "R9") (pin "P$1") (pinfunction "P$1_P$1") (pintype "bidirectional"))
      (node (ref "U7") (pin "1") (pinfunction "FB_1") (pintype "bidirectional"))
    )
    (net (code "45") (name "Net-(U7-VCC)") (class "Default")
      (node (ref "C26") (pin "P$1") (pinfunction "P$1_P$1") (pintype "bidirectional"))
      (node (ref "U7") (pin "2") (pinfunction "VCC_2") (pintype "bidirectional"))
    )
    (net (code "46") (name "RSLV_A0") (class "Default")
      (node (ref "U2") (pin "37") (pinfunction "A0_37") (pintype "bidirectional"))
    )
    (net (code "47") (name "RSLV_A1") (class "Default")
      (node (ref "U2") (pin "36") (pinfunction "A1_36") (pintype "bidirectional"))
    )
    (net (code "48") (name "RSLV_DOS") (class "Default")
      (node (ref "U2") (pin "35") (pinfunction "DOS_35") (pintype "bidirectional"))
    )
    (net (code "49") (name "RSLV_LOT") (class "Default")
      (node (ref "U2") (pin "34") (pinfunction "LOT_34") (pintype "bidirectional"))
    )
    (net (code "50") (name "RSLV_MISO") (class "Default")
      (node (ref "U2") (pin "11") (pinfunction "DB15/SDO_11") (pintype "bidirectional"))
    )
    (net (code "51") (name "RSLV_MOSI") (class "Default")
      (node (ref "U2") (pin "12") (pinfunction "DB14/SDI_12") (pintype "bidirectional"))
    )
    (net (code "52") (name "RSLV_SAMPLE") (class "Default")
      (node (ref "U2") (pin "10") (pinfunction "~{SAMPLE}_10") (pintype "bidirectional"))
    )
    (net (code "53") (name "RSLV_SCK") (class "Default")
      (node (ref "U2") (pin "13") (pinfunction "DB13/SCK_13") (pintype "bidirectional"))
    )
    (net (code "54") (name "SWCLK") (class "Default")
      (node (ref "TC1") (pin "4") (pinfunction "S_4") (pintype "passive"))
      (node (ref "U1") (pin "76") (pinfunction "PF0_76") (pintype "bidirectional"))
    )
    (net (code "55") (name "SWDIO") (class "Default")
      (node (ref "TC1") (pin "2") (pinfunction "S_2") (pintype "passive"))
      (node (ref "U1") (pin "77") (pinfunction "PF1_77") (pintype "bidirectional"))
    )
    (net (code "56") (name "SWO") (class "Default")
      (node (ref "TC1") (pin "6") (pinfunction "S_6") (pintype "passive"))
      (node (ref "U1") (pin "78") (pinfunction "PF2_78") (pintype "bidirectional"))
    )
    (net (code "57") (name "UH") (class "Default")
      (node (ref "J5") (pin "1") (pinfunction "S_1") (pintype "passive"))
    )
    (net (code "58") (name "UL") (class "Default")
      (node (ref "J5") (pin "2") (pinfunction "S_2") (pintype "passive"))
    )
    (net (code "59") (name "V+") (class "Default")
      (node (ref "U8") (pin "8") (pinfunction "V+_8") (pintype "power_in"))
    )
    (net (code "60") (name "V-") (class "Default")
      (node (ref "U8") (pin "4") (pinfunction "V-_4") (pintype "power_in"))
    )
    (net (code "61") (name "VH") (class "Default")
      (node (ref "J5") (pin "3") (pinfunction "S_3") (pintype "passive"))
    )
    (net (code "62") (name "VIN_FB") (class "Default")
      (node (ref "C28") (pin "P$1") (pinfunction "P$1_P$1") (pintype "bidirectional"))
      (node (ref "R11") (pin "P$1") (pinfunction "P$1_P$1") (pintype "bidirectional"))
      (node (ref "R12") (pin "P$2") (pinfunction "P$2_P$2") (pintype "bidirectional"))
    )
    (net (code "63") (name "VL") (class "Default")
      (node (ref "J5") (pin "4") (pinfunction "S_4") (pintype "passive"))
    )
    (net (code "64") (name "WH") (class "Default")
      (node (ref "J5") (pin "5") (pinfunction "S_5") (pintype "passive"))
    )
    (net (code "65") (name "WL") (class "Default")
      (node (ref "J5") (pin "6") (pinfunction "S_6") (pintype "passive"))
    )
    (net (code "66") (name "unconnected-(D1-CLKO-Pad6)") (class "Default")
      (node (ref "D1") (pin "6") (pinfunction "CLKO_6") (pintype "bidirectional"))
    )
    (net (code "67") (name "unconnected-(D1-SDO-Pad1)") (class "Default")
      (node (ref "D1") (pin "1") (pinfunction "SDO_1") (pintype "bidirectional"))
    )
    (net (code "68") (name "unconnected-(SW1-Pad1)") (class "Default")
      (node (ref "SW1") (pin "1") (pinfunction "1_1") (pintype "passive"))
    )
    (net (code "69") (name "unconnected-(TC1F-S-Pad5)") (class "Default")
      (node (ref "TC1") (pin "5") (pinfunction "S_5") (pintype "passive"))
    )
    (net (code "70") (name "unconnected-(TC1H-S-Pad7)") (class "Default")
      (node (ref "TC1") (pin "7") (pinfunction "S_7") (pintype "passive"))
    )
    (net (code "71") (name "unconnected-(TC1I-S-Pad8)") (class "Default")
      (node (ref "TC1") (pin "8") (pinfunction "S_8") (pintype "passive"))
    )
    (net (code "72") (name "unconnected-(TC1J-S-Pad9)") (class "Default")
      (node (ref "TC1") (pin "9") (pinfunction "S_9") (pintype "passive"))
    )
    (net (code "73") (name "unconnected-(U1-PA0-Pad1)") (class "Default")
      (node (ref "U1") (pin "1") (pinfunction "PA0_1") (pintype "bidirectional"))
    )
    (net (code "74") (name "unconnected-(U1-PA1-Pad2)") (class "Default")
      (node (ref "U1") (pin "2") (pinfunction "PA1_2") (pintype "bidirectional"))
    )
    (net (code "75") (name "unconnected-(U1-PA2-Pad3)") (class "Default")
      (node (ref "U1") (pin "3") (pinfunction "PA2_3") (pintype "bidirectional"))
    )
    (net (code "76") (name "unconnected-(U1-PA3-Pad4)") (class "Default")
      (node (ref "U1") (pin "4") (pinfunction "PA3_4") (pintype "bidirectional"))
    )
    (net (code "77") (name "unconnected-(U1-PA4-Pad5)") (class "Default")
      (node (ref "U1") (pin "5") (pinfunction "PA4_5") (pintype "bidirectional"))
    )
    (net (code "78") (name "unconnected-(U1-PA5-Pad6)") (class "Default")
      (node (ref "U1") (pin "6") (pinfunction "PA5_6") (pintype "bidirectional"))
    )
    (net (code "79") (name "unconnected-(U1-PA6-Pad7)") (class "Default")
      (node (ref "U1") (pin "7") (pinfunction "PA6_7") (pintype "bidirectional"))
    )
    (net (code "80") (name "unconnected-(U1-PA7-Pad26)") (class "Default")
      (node (ref "U1") (pin "26") (pinfunction "PA7_26") (pintype "bidirectional"))
    )
    (net (code "81") (name "unconnected-(U1-PA8-Pad27)") (class "Default")
      (node (ref "U1") (pin "27") (pinfunction "PA8_27") (pintype "bidirectional"))
    )
    (net (code "82") (name "unconnected-(U1-PA9-Pad28)") (class "Default")
      (node (ref "U1") (pin "28") (pinfunction "PA9_28") (pintype "bidirectional"))
    )
    (net (code "83") (name "unconnected-(U1-PA10-Pad29)") (class "Default")
      (node (ref "U1") (pin "29") (pinfunction "PA10_29") (pintype "bidirectional"))
    )
    (net (code "84") (name "unconnected-(U1-PA11-Pad30)") (class "Default")
      (node (ref "U1") (pin "30") (pinfunction "PA11_30") (pintype "bidirectional"))
    )
    (net (code "85") (name "unconnected-(U1-PA12-Pad33)") (class "Default")
      (node (ref "U1") (pin "33") (pinfunction "PA12_33") (pintype "bidirectional"))
    )
    (net (code "86") (name "unconnected-(U1-PA13-Pad34)") (class "Default")
      (node (ref "U1") (pin "34") (pinfunction "PA13_34") (pintype "bidirectional"))
    )
    (net (code "87") (name "unconnected-(U1-PA14-Pad35)") (class "Default")
      (node (ref "U1") (pin "35") (pinfunction "PA14_35") (pintype "bidirectional"))
    )
    (net (code "88") (name "unconnected-(U1-PA15-Pad100)") (class "Default")
      (node (ref "U1") (pin "100") (pinfunction "PA15_100") (pintype "bidirectional"))
    )
    (net (code "89") (name "unconnected-(U1-PB0-Pad9)") (class "Default")
      (node (ref "U1") (pin "9") (pinfunction "PB0_9") (pintype "bidirectional"))
    )
    (net (code "90") (name "unconnected-(U1-PB1-Pad10)") (class "Default")
      (node (ref "U1") (pin "10") (pinfunction "PB1_10") (pintype "bidirectional"))
    )
    (net (code "91") (name "unconnected-(U1-PB2-Pad11)") (class "Default")
      (node (ref "U1") (pin "11") (pinfunction "PB2_11") (pintype "bidirectional"))
    )
    (net (code "92") (name "unconnected-(U1-PB3-Pad12)") (class "Default")
      (node (ref "U1") (pin "12") (pinfunction "PB3_12") (pintype "bidirectional"))
    )
    (net (code "93") (name "unconnected-(U1-PB4-Pad13)") (class "Default")
      (node (ref "U1") (pin "13") (pinfunction "PB4_13") (pintype "bidirectional"))
    )
    (net (code "94") (name "unconnected-(U1-PB5-Pad14)") (class "Default")
      (node (ref "U1") (pin "14") (pinfunction "PB5_14") (pintype "bidirectional"))
    )
    (net (code "95") (name "unconnected-(U1-PB6-Pad15)") (class "Default")
      (node (ref "U1") (pin "15") (pinfunction "PB6_15") (pintype "bidirectional"))
    )
    (net (code "96") (name "unconnected-(U1-PB9-Pad37)") (class "Default")
      (node (ref "U1") (pin "37") (pinfunction "PB9_37") (pintype "bidirectional"))
    )
    (net (code "97") (name "unconnected-(U1-PB10-Pad38)") (class "Default")
      (node (ref "U1") (pin "38") (pinfunction "PB10_38") (pintype "bidirectional"))
    )
    (net (code "98") (name "unconnected-(U1-PB11-Pad39)") (class "Default")
      (node (ref "U1") (pin "39") (pinfunction "PB11_39") (pintype "bidirectional"))
    )
    (net (code "99") (name "unconnected-(U1-PB12-Pad40)") (class "Default")
      (node (ref "U1") (pin "40") (pinfunction "PB12_40") (pintype "bidirectional"))
    )
    (net (code "100") (name "unconnected-(U1-PC0-Pad18)") (class "Default")
      (node (ref "U1") (pin "18") (pinfunction "PC0_18") (pintype "bidirectional"))
    )
    (net (code "101") (name "unconnected-(U1-PC1-Pad19)") (class "Default")
      (node (ref "U1") (pin "19") (pinfunction "PC1_19") (pintype "bidirectional"))
    )
    (net (code "102") (name "unconnected-(U1-PC2-Pad20)") (class "Default")
      (node (ref "U1") (pin "20") (pinfunction "PC2_20") (pintype "bidirectional"))
    )
    (net (code "103") (name "unconnected-(U1-PC3-Pad21)") (class "Default")
      (node (ref "U1") (pin "21") (pinfunction "PC3_21") (pintype "bidirectional"))
    )
    (net (code "104") (name "unconnected-(U1-PC4-Pad22)") (class "Default")
      (node (ref "U1") (pin "22") (pinfunction "PC4_22") (pintype "bidirectional"))
    )
    (net (code "105") (name "unconnected-(U1-PC5-Pad23)") (class "Default")
      (node (ref "U1") (pin "23") (pinfunction "PC5_23") (pintype "bidirectional"))
    )
    (net (code "106") (name "unconnected-(U1-PC7-Pad54)") (class "Default")
      (node (ref "U1") (pin "54") (pinfunction "PC7_54") (pintype "bidirectional"))
    )
    (net (code "107") (name "unconnected-(U1-PC8-Pad68)") (class "Default")
      (node (ref "U1") (pin "68") (pinfunction "PC8_68") (pintype "bidirectional"))
    )
    (net (code "108") (name "unconnected-(U1-PC9-Pad69)") (class "Default")
      (node (ref "U1") (pin "69") (pinfunction "PC9_69") (pintype "bidirectional"))
    )
    (net (code "109") (name "unconnected-(U1-PC10-Pad70)") (class "Default")
      (node (ref "U1") (pin "70") (pinfunction "PC10_70") (pintype "bidirectional"))
    )
    (net (code "110") (name "unconnected-(U1-PC11-Pad71)") (class "Default")
      (node (ref "U1") (pin "71") (pinfunction "PC11_71") (pintype "bidirectional"))
    )
    (net (code "111") (name "unconnected-(U1-PD0-Pad45)") (class "Default")
      (node (ref "U1") (pin "45") (pinfunction "PD0_45") (pintype "bidirectional"))
    )
    (net (code "112") (name "unconnected-(U1-PD1-Pad46)") (class "Default")
      (node (ref "U1") (pin "46") (pinfunction "PD1_46") (pintype "bidirectional"))
    )
    (net (code "113") (name "unconnected-(U1-PD2-Pad47)") (class "Default")
      (node (ref "U1") (pin "47") (pinfunction "PD2_47") (pintype "bidirectional"))
    )
    (net (code "114") (name "unconnected-(U1-PD3-Pad48)") (class "Default")
      (node (ref "U1") (pin "48") (pinfunction "PD3_48") (pintype "bidirectional"))
    )
    (net (code "115") (name "unconnected-(U1-PD4-Pad49)") (class "Default")
      (node (ref "U1") (pin "49") (pinfunction "PD4_49") (pintype "bidirectional"))
    )
    (net (code "116") (name "unconnected-(U1-PD5-Pad50)") (class "Default")
      (node (ref "U1") (pin "50") (pinfunction "PD5_50") (pintype "bidirectional"))
    )
    (net (code "117") (name "unconnected-(U1-PD6-Pad51)") (class "Default")
      (node (ref "U1") (pin "51") (pinfunction "PD6_51") (pintype "bidirectional"))
    )
    (net (code "118") (name "unconnected-(U1-PD7-Pad52)") (class "Default")
      (node (ref "U1") (pin "52") (pinfunction "PD7_52") (pintype "bidirectional"))
    )
    (net (code "119") (name "unconnected-(U1-PD8-Pad53)") (class "Default")
      (node (ref "U1") (pin "53") (pinfunction "PD8_53") (pintype "bidirectional"))
    )
    (net (code "120") (name "unconnected-(U1-PD9-Pad88)") (class "Default")
      (node (ref "U1") (pin "88") (pinfunction "PD9_88") (pintype "bidirectional"))
    )
    (net (code "121") (name "unconnected-(U1-PD10-Pad89)") (class "Default")
      (node (ref "U1") (pin "89") (pinfunction "PD10_89") (pintype "bidirectional"))
    )
    (net (code "122") (name "unconnected-(U1-PD11-Pad90)") (class "Default")
      (node (ref "U1") (pin "90") (pinfunction "PD11_90") (pintype "bidirectional"))
    )
    (net (code "123") (name "unconnected-(U1-PD12-Pad91)") (class "Default")
      (node (ref "U1") (pin "91") (pinfunction "PD12_91") (pintype "bidirectional"))
    )
    (net (code "124") (name "unconnected-(U1-PE1-Pad61)") (class "Default")
      (node (ref "U1") (pin "61") (pinfunction "PE1_61") (pintype "bidirectional"))
    )
    (net (code "125") (name "unconnected-(U1-PE2-Pad62)") (class "Default")
      (node (ref "U1") (pin "62") (pinfunction "PE2_62") (pintype "bidirectional"))
    )
    (net (code "126") (name "unconnected-(U1-PE3-Pad63)") (class "Default")
      (node (ref "U1") (pin "63") (pinfunction "PE3_63") (pintype "bidirectional"))
    )
    (net (code "127") (name "unconnected-(U1-PE4-Pad64)") (class "Default")
      (node (ref "U1") (pin "64") (pinfunction "PE4_64") (pintype "bidirectional"))
    )
    (net (code "128") (name "unconnected-(U1-PE5-Pad65)") (class "Default")
      (node (ref "U1") (pin "65") (pinfunction "PE5_65") (pintype "bidirectional"))
    )
    (net (code "129") (name "unconnected-(U1-PE6-Pad66)") (class "Default")
      (node (ref "U1") (pin "66") (pinfunction "PE6_66") (pintype "bidirectional"))
    )
    (net (code "130") (name "unconnected-(U1-PE7-Pad67)") (class "Default")
      (node (ref "U1") (pin "67") (pinfunction "PE7_67") (pintype "bidirectional"))
    )
    (net (code "131") (name "unconnected-(U1-PE8-Pad92)") (class "Default")
      (node (ref "U1") (pin "92") (pinfunction "PE8_92") (pintype "bidirectional"))
    )
    (net (code "132") (name "unconnected-(U1-PE9-Pad93)") (class "Default")
      (node (ref "U1") (pin "93") (pinfunction "PE9_93") (pintype "bidirectional"))
    )
    (net (code "133") (name "unconnected-(U1-PE10-Pad94)") (class "Default")
      (node (ref "U1") (pin "94") (pinfunction "PE10_94") (pintype "bidirectional"))
    )
    (net (code "134") (name "unconnected-(U1-PE11-Pad95)") (class "Default")
      (node (ref "U1") (pin "95") (pinfunction "PE11_95") (pintype "bidirectional"))
    )
    (net (code "135") (name "unconnected-(U1-PE12-Pad96)") (class "Default")
      (node (ref "U1") (pin "96") (pinfunction "PE12_96") (pintype "bidirectional"))
    )
    (net (code "136") (name "unconnected-(U1-PE13-Pad97)") (class "Default")
      (node (ref "U1") (pin "97") (pinfunction "PE13_97") (pintype "bidirectional"))
    )
    (net (code "137") (name "unconnected-(U1-PE14-Pad98)") (class "Default")
      (node (ref "U1") (pin "98") (pinfunction "PE14_98") (pintype "bidirectional"))
    )
    (net (code "138") (name "unconnected-(U1-PE15-Pad99)") (class "Default")
      (node (ref "U1") (pin "99") (pinfunction "PE15_99") (pintype "bidirectional"))
    )
    (net (code "139") (name "unconnected-(U1-PF5-Pad81)") (class "Default")
      (node (ref "U1") (pin "81") (pinfunction "PF5_81") (pintype "bidirectional"))
    )
    (net (code "140") (name "unconnected-(U1-PF6-Pad84)") (class "Default")
      (node (ref "U1") (pin "84") (pinfunction "PF6_84") (pintype "bidirectional"))
    )
    (net (code "141") (name "unconnected-(U1-PF7-Pad85)") (class "Default")
      (node (ref "U1") (pin "85") (pinfunction "PF7_85") (pintype "bidirectional"))
    )
    (net (code "142") (name "unconnected-(U1-PF8-Pad86)") (class "Default")
      (node (ref "U1") (pin "86") (pinfunction "PF8_86") (pintype "bidirectional"))
    )
    (net (code "143") (name "unconnected-(U1-PF9-Pad87)") (class "Default")
      (node (ref "U1") (pin "87") (pinfunction "PF9_87") (pintype "bidirectional"))
    )
    (net (code "144") (name "unconnected-(U1-PF10-Pad74)") (class "Default")
      (node (ref "U1") (pin "74") (pinfunction "PF10_74") (pintype "bidirectional"))
    )
    (net (code "145") (name "unconnected-(U1-PF11-Pad75)") (class "Default")
      (node (ref "U1") (pin "75") (pinfunction "PF11_75") (pintype "bidirectional"))
    )
    (net (code "146") (name "unconnected-(U1-PF12-Pad80)") (class "Default")
      (node (ref "U1") (pin "80") (pinfunction "PF12_80") (pintype "bidirectional"))
    )
    (net (code "147") (name "unconnected-(U1-VBUS-Pad79)") (class "Default")
      (node (ref "U1") (pin "79") (pinfunction "VBUS_79") (pintype "bidirectional"))
    )
    (net (code "148") (name "unconnected-(U2B-DB0-Pad28)") (class "Default")
      (node (ref "U2") (pin "28") (pinfunction "DB0_28") (pintype "bidirectional"))
    )
    (net (code "149") (name "unconnected-(U2B-DB1-Pad27)") (class "Default")
      (node (ref "U2") (pin "27") (pinfunction "DB1_27") (pintype "bidirectional"))
    )
    (net (code "150") (name "unconnected-(U2B-DB2-Pad26)") (class "Default")
      (node (ref "U2") (pin "26") (pinfunction "DB2_26") (pintype "bidirectional"))
    )
    (net (code "151") (name "unconnected-(U2B-DB3-Pad25)") (class "Default")
      (node (ref "U2") (pin "25") (pinfunction "DB3_25") (pintype "bidirectional"))
    )
    (net (code "152") (name "unconnected-(U2B-DB4-Pad24)") (class "Default")
      (node (ref "U2") (pin "24") (pinfunction "DB4_24") (pintype "bidirectional"))
    )
    (net (code "153") (name "unconnected-(U2B-DB5-Pad23)") (class "Default")
      (node (ref "U2") (pin "23") (pinfunction "DB5_23") (pintype "bidirectional"))
    )
    (net (code "154") (name "unconnected-(U2B-DB6-Pad22)") (class "Default")
      (node (ref "U2") (pin "22") (pinfunction "DB6_22") (pintype "bidirectional"))
    )
    (net (code "155") (name "unconnected-(U2B-DB7-Pad21)") (class "Default")
      (node (ref "U2") (pin "21") (pinfunction "DB7_21") (pintype "bidirectional"))
    )
    (net (code "156") (name "unconnected-(U2B-DB8-Pad20)") (class "Default")
      (node (ref "U2") (pin "20") (pinfunction "DB8_20") (pintype "bidirectional"))
    )
    (net (code "157") (name "unconnected-(U2B-DB9-Pad17)") (class "Default")
      (node (ref "U2") (pin "17") (pinfunction "DB9_17") (pintype "bidirectional"))
    )
    (net (code "158") (name "unconnected-(U2B-DB10-Pad16)") (class "Default")
      (node (ref "U2") (pin "16") (pinfunction "DB10_16") (pintype "bidirectional"))
    )
    (net (code "159") (name "unconnected-(U2B-DB11-Pad15)") (class "Default")
      (node (ref "U2") (pin "15") (pinfunction "DB11_15") (pintype "bidirectional"))
    )
    (net (code "160") (name "unconnected-(U2B-DB12-Pad14)") (class "Default")
      (node (ref "U2") (pin "14") (pinfunction "DB12_14") (pintype "bidirectional"))
    )
    (net (code "161") (name "unconnected-(U2C-A-Pad29)") (class "Default")
      (node (ref "U2") (pin "29") (pinfunction "A_29") (pintype "bidirectional"))
    )
    (net (code "162") (name "unconnected-(U2C-B-Pad30)") (class "Default")
      (node (ref "U2") (pin "30") (pinfunction "B_30") (pintype "bidirectional"))
    )
    (net (code "163") (name "unconnected-(U2C-DIR-Pad32)") (class "Default")
      (node (ref "U2") (pin "32") (pinfunction "DIR_32") (pintype "bidirectional"))
    )
    (net (code "164") (name "unconnected-(U2C-NM-Pad31)") (class "Default")
      (node (ref "U2") (pin "31") (pinfunction "NM_31") (pintype "bidirectional"))
    )
    (net (code "165") (name "unconnected-(U2E-REFOUT-Pad47)") (class "Default")
      (node (ref "U2") (pin "47") (pinfunction "REFOUT_47") (pintype "bidirectional"))
    )
    (net (code "166") (name "unconnected-(U8A--IN-Pad2)") (class "Default")
      (node (ref "U8") (pin "2") (pinfunction "-IN_2") (pintype "input"))
    )
    (net (code "167") (name "~{RSLV_CS}") (class "Default")
      (node (ref "U2") (pin "2") (pinfunction "~{CS}_2") (pintype "bidirectional"))
    )
    (net (code "168") (name "~{RSLV_RD}") (class "Default")
      (node (ref "U2") (pin "3") (pinfunction "~{RD}_3") (pintype "bidirectional"))
    )
    (net (code "169") (name "~{RSLV_RST}") (class "Default")
      (node (ref "U2") (pin "33") (pinfunction "~{RESET}_33") (pintype "bidirectional"))
    )
    (net (code "170") (name "~{RSLV_WR}") (class "Default")
      (node (ref "U2") (pin "4") (pinfunction "~{WR/FSYNC}_4") (pintype "bidirectional"))
    )
    (net (code "171") (name "~{RST}") (class "Default")
      (node (ref "C15") (pin "P$2") (pinfunction "P$2_P$2") (pintype "bidirectional"))
      (node (ref "R1") (pin "P$2") (pinfunction "P$2_P$2") (pintype "bidirectional"))
      (node (ref "SW1") (pin "2") (pinfunction "2_2") (pintype "passive"))
      (node (ref "TC1") (pin "10") (pinfunction "S_10") (pintype "passive"))
      (node (ref "U1") (pin "36") (pinfunction "~{RESET}_36") (pintype "bidirectional"))
    )
  )
)
